# SaLAltimeter_1_5.net
KiCad netlist of a schematic drawn in EAGLE
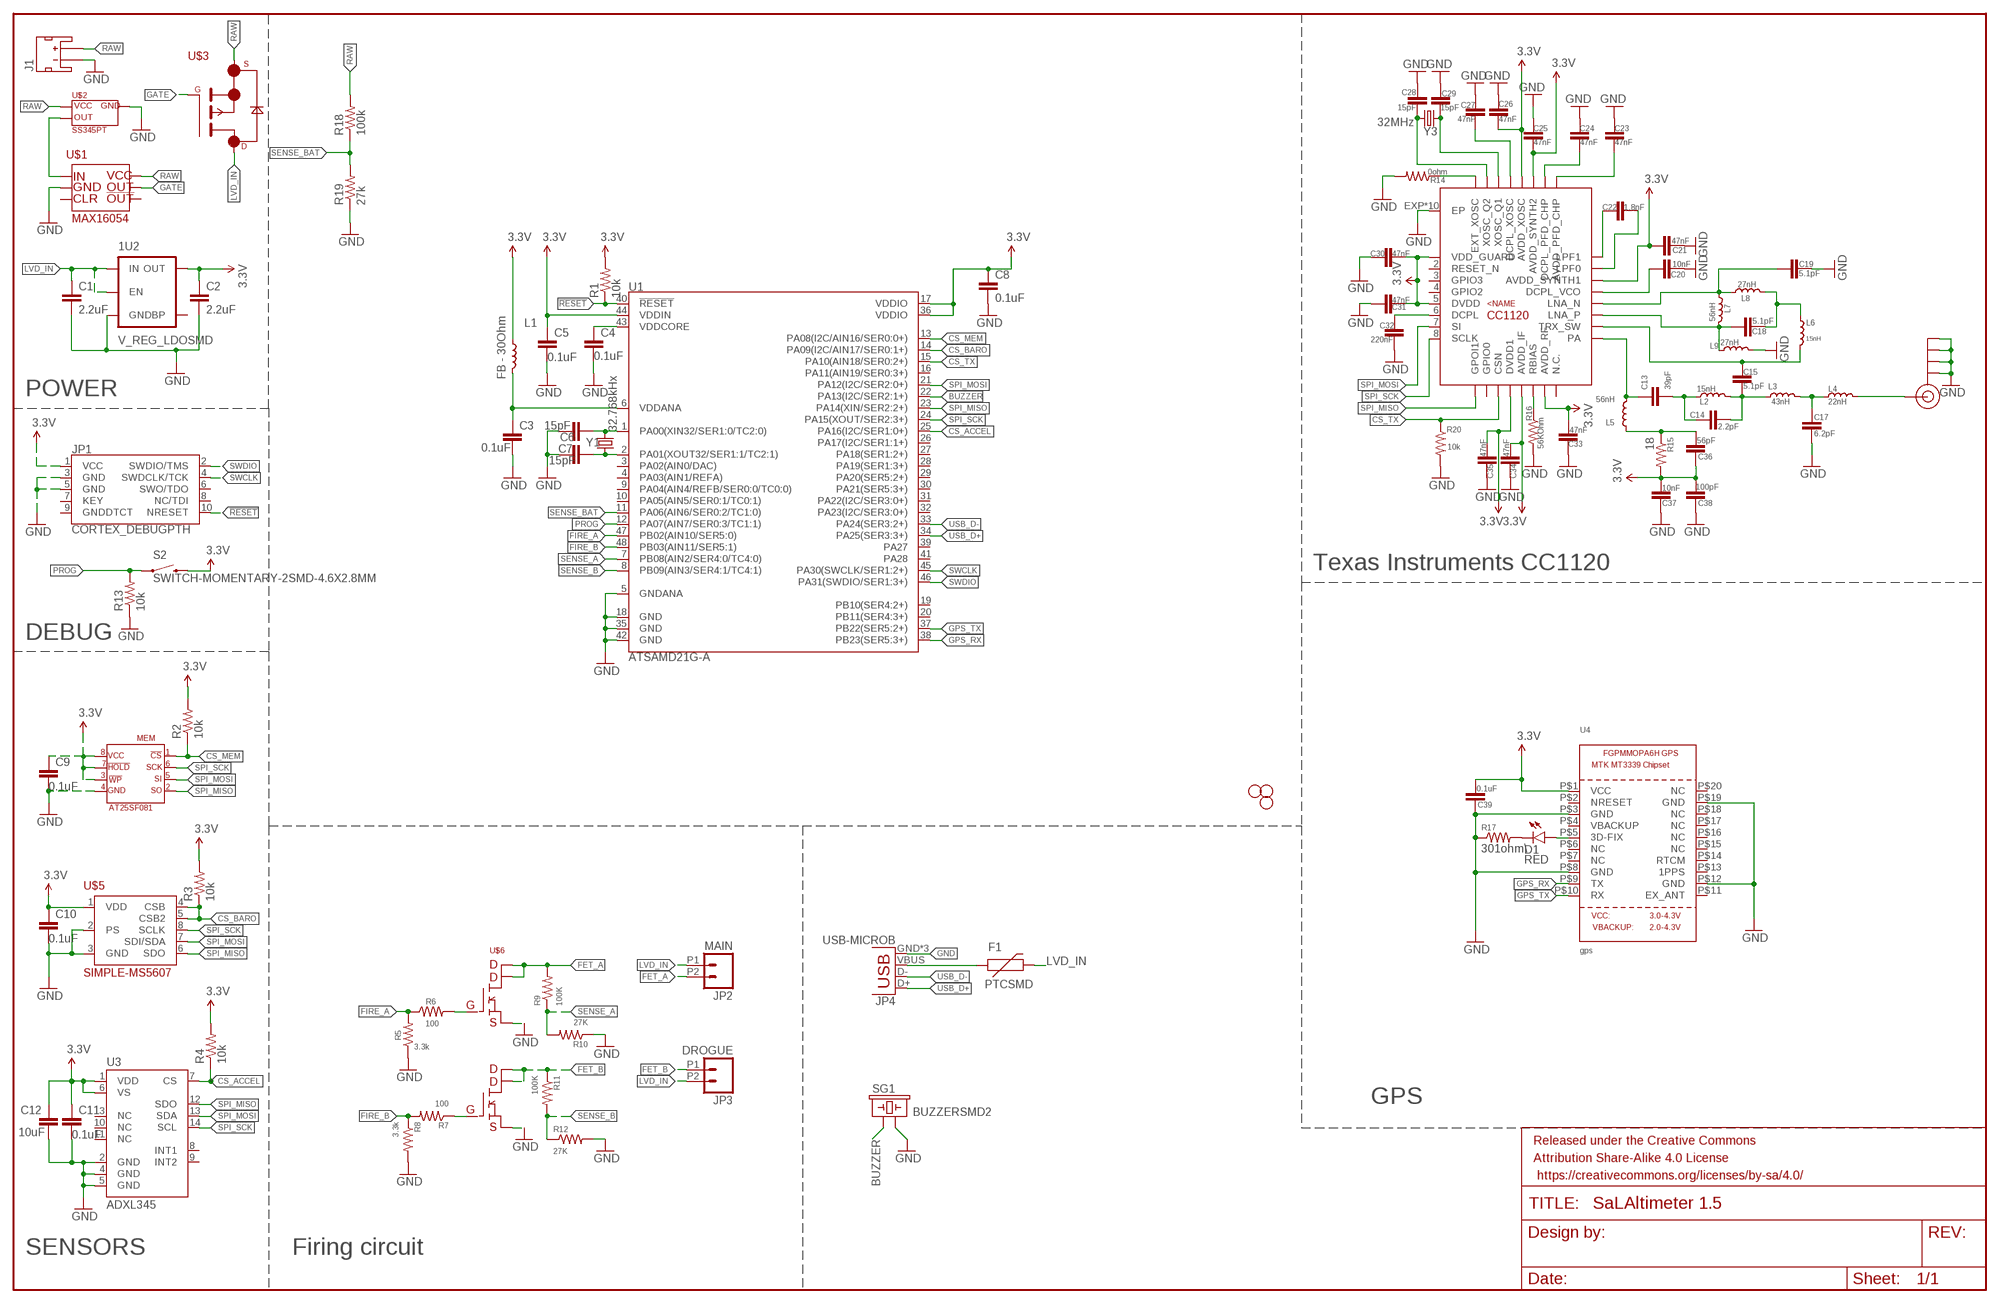
[diagram p0: schematic, sheet 1]

(export (version "E")
  (design (tool "Eeschema 10.0.6"))
  (components
    (comp (ref "1U2")
      (value "V_REG_LDOSMD")
      (footprint "eagle-import:SOT23-5")
      (libsource (lib "eagle-import") (part "V_REG_LDOSMD"))
    )
    (comp (ref "C1")
      (value "2.2uF")
      (footprint "eagle-import:0603-CAP")
      (libsource (lib "eagle-import") (part "CAP0603-CAP"))
    )
    (comp (ref "C2")
      (value "2.2uF")
      (footprint "eagle-import:0603-CAP")
      (libsource (lib "eagle-import") (part "CAP0603-CAP"))
    )
    (comp (ref "C3")
      (value "0.1uF")
      (footprint "eagle-import:0402-CAP")
      (libsource (lib "eagle-import") (part "SparkFun-Passives_CAP0402-CAP"))
    )
    (comp (ref "C4")
      (value "0.1uF")
      (footprint "eagle-import:0402-CAP")
      (libsource (lib "eagle-import") (part "SparkFun-Passives_CAP0402-CAP"))
    )
    (comp (ref "C5")
      (value "0.1uF")
      (footprint "eagle-import:0402-CAP")
      (libsource (lib "eagle-import") (part "SparkFun-Passives_CAP0402-CAP"))
    )
    (comp (ref "C6")
      (value "15pF")
      (footprint "eagle-import:0402-CAP")
      (libsource (lib "eagle-import") (part "SparkFun-Passives_CAP0402-CAP"))
    )
    (comp (ref "C7")
      (value "15pF")
      (footprint "eagle-import:0402-CAP")
      (libsource (lib "eagle-import") (part "SparkFun-Passives_CAP0402-CAP"))
    )
    (comp (ref "C8")
      (value "0.1uF")
      (footprint "eagle-import:0402-CAP")
      (libsource (lib "eagle-import") (part "SparkFun-Passives_CAP0402-CAP"))
    )
    (comp (ref "C9")
      (value "0.1uF")
      (footprint "eagle-import:0402-CAP")
      (libsource (lib "eagle-import") (part "SparkFun-Passives_CAP0402-CAP"))
    )
    (comp (ref "C10")
      (value "0.1uF")
      (footprint "eagle-import:0402-CAP")
      (libsource (lib "eagle-import") (part "SparkFun-Passives_CAP0402-CAP"))
    )
    (comp (ref "C11")
      (value "0.1uF")
      (footprint "eagle-import:0402-CAP")
      (libsource (lib "eagle-import") (part "SparkFun-Passives_CAP0402-CAP"))
    )
    (comp (ref "C12")
      (value "10uF")
      (footprint "eagle-import:0402-CAP")
      (libsource (lib "eagle-import") (part "SparkFun-Passives_CAP0402-CAP"))
    )
    (comp (ref "C13")
      (value "39pF")
      (footprint "eagle-import:0402-CAP")
      (libsource (lib "eagle-import") (part "CAP0402-CAP"))
    )
    (comp (ref "C14")
      (value "2.2pF")
      (footprint "eagle-import:0402-CAP")
      (libsource (lib "eagle-import") (part "CAP0402-CAP"))
    )
    (comp (ref "C15")
      (value "5.1pF")
      (footprint "eagle-import:0402-CAP")
      (libsource (lib "eagle-import") (part "CAP0402-CAP"))
    )
    (comp (ref "C17")
      (value "6.2pF")
      (footprint "eagle-import:0402-CAP")
      (libsource (lib "eagle-import") (part "CAP0402-CAP"))
    )
    (comp (ref "C18")
      (value "5.1pF")
      (footprint "eagle-import:0402-CAP")
      (libsource (lib "eagle-import") (part "CAP0402-CAP"))
    )
    (comp (ref "C19")
      (value "5.1pF")
      (footprint "eagle-import:0402-CAP")
      (libsource (lib "eagle-import") (part "CAP0402-CAP"))
    )
    (comp (ref "C20")
      (value "10nF")
      (footprint "eagle-import:0402-CAP")
      (libsource (lib "eagle-import") (part "CAP0402-CAP"))
    )
    (comp (ref "C21")
      (value "47nF")
      (footprint "eagle-import:0402-CAP")
      (libsource (lib "eagle-import") (part "CAP0402-CAP"))
    )
    (comp (ref "C22")
      (value "1.8nF")
      (footprint "eagle-import:0402-CAP")
      (libsource (lib "eagle-import") (part "CAP0402-CAP"))
    )
    (comp (ref "C23")
      (value "47nF")
      (footprint "eagle-import:0402-CAP")
      (libsource (lib "eagle-import") (part "CAP0402-CAP"))
    )
    (comp (ref "C24")
      (value "47nF")
      (footprint "eagle-import:0402-CAP")
      (libsource (lib "eagle-import") (part "CAP0402-CAP"))
    )
    (comp (ref "C25")
      (value "47nF")
      (footprint "eagle-import:0402-CAP")
      (libsource (lib "eagle-import") (part "CAP0402-CAP"))
    )
    (comp (ref "C26")
      (value "47nF")
      (footprint "eagle-import:0402-CAP")
      (libsource (lib "eagle-import") (part "CAP0402-CAP"))
    )
    (comp (ref "C27")
      (value "47nF")
      (footprint "eagle-import:0402-CAP")
      (libsource (lib "eagle-import") (part "CAP0402-CAP"))
    )
    (comp (ref "C28")
      (value "15pF")
      (footprint "eagle-import:0402-CAP")
      (libsource (lib "eagle-import") (part "CAP0402-CAP"))
    )
    (comp (ref "C29")
      (value "15pF")
      (footprint "eagle-import:0402-CAP")
      (libsource (lib "eagle-import") (part "CAP0402-CAP"))
    )
    (comp (ref "C30")
      (value "47nF")
      (footprint "eagle-import:0402-CAP")
      (libsource (lib "eagle-import") (part "CAP0402-CAP"))
    )
    (comp (ref "C31")
      (value "47nF")
      (footprint "eagle-import:0402-CAP")
      (libsource (lib "eagle-import") (part "CAP0402-CAP"))
    )
    (comp (ref "C32")
      (value "220nF")
      (footprint "eagle-import:0402-CAP")
      (libsource (lib "eagle-import") (part "CAP0402-CAP"))
    )
    (comp (ref "C33")
      (value "47nF")
      (footprint "eagle-import:0402-CAP")
      (libsource (lib "eagle-import") (part "CAP0402-CAP"))
    )
    (comp (ref "C34")
      (value "47nF")
      (footprint "eagle-import:0402-CAP")
      (libsource (lib "eagle-import") (part "CAP0402-CAP"))
    )
    (comp (ref "C35")
      (value "47nF")
      (footprint "eagle-import:0402-CAP")
      (libsource (lib "eagle-import") (part "CAP0402-CAP"))
    )
    (comp (ref "C36")
      (value "56pF")
      (footprint "eagle-import:0402-CAP")
      (libsource (lib "eagle-import") (part "CAP0402-CAP"))
    )
    (comp (ref "C37")
      (value "10nF")
      (footprint "eagle-import:0402-CAP")
      (libsource (lib "eagle-import") (part "CAP0402-CAP"))
    )
    (comp (ref "C38")
      (value "100pF")
      (footprint "eagle-import:0402-CAP")
      (libsource (lib "eagle-import") (part "CAP0402-CAP"))
    )
    (comp (ref "C39")
      (value "0.1uF")
      (footprint "eagle-import:0402-CAP")
      (libsource (lib "eagle-import") (part "CAP0402-CAP"))
    )
    (comp (ref "D1")
      (value "RED")
      (footprint "eagle-import:LED-0603")
      (libsource (lib "eagle-import") (part "LED-RED0603"))
    )
    (comp (ref "F1")
      (value "PTCSMD")
      (footprint "eagle-import:PTC-1206")
      (libsource (lib "eagle-import") (part "PTCSMD"))
    )
    (comp (ref "FRAME1")
      (value "FRAME-LEDGER")
      (footprint "eagle-import:CREATIVE_COMMONS")
      (libsource (lib "eagle-import") (part "FRAME-LEDGER"))
    )
    (comp (ref "J$1")
      (value "SMA_EDGE")
      (footprint "eagle-import:SMA-EDGE")
      (libsource (lib "eagle-import") (part "SMA_EDGE"))
    )
    (comp (ref "J1")
      (value "BAT")
      (footprint "eagle-import:JST-2-SMD")
      (libsource (lib "eagle-import") (part "JST_2MM_MALE"))
    )
    (comp (ref "JP1")
      (value "CORTEX_DEBUGPTH")
      (footprint "eagle-import:2X5-PTH-1.27MM")
      (libsource (lib "eagle-import") (part "CORTEX_DEBUGPTH"))
    )
    (comp (ref "JP2")
      (value "MAIN")
      (footprint "eagle-import:1X02_2.54_SCREWTERM")
      (libsource (lib "eagle-import") (part "M022.54MM_SCREWTERM"))
    )
    (comp (ref "JP3")
      (value "DROGUE")
      (footprint "eagle-import:1X02_2.54_SCREWTERM")
      (libsource (lib "eagle-import") (part "M022.54MM_SCREWTERM"))
    )
    (comp (ref "JP4")
      (value "USB-MICROB")
      (footprint "eagle-import:USB-MICROB")
      (libsource (lib "eagle-import") (part "USB-MICROB"))
    )
    (comp (ref "L1")
      (value "FB - 30Ohm")
      (footprint "eagle-import:0603")
      (libsource (lib "eagle-import") (part "INDUCTOR0603"))
    )
    (comp (ref "L2")
      (value "15nH")
      (footprint "eagle-import:C0402")
      (libsource (lib "eagle-import") (part "INDUCTOR0402"))
    )
    (comp (ref "L3")
      (value "43nH")
      (footprint "eagle-import:C0402")
      (libsource (lib "eagle-import") (part "INDUCTOR0402"))
    )
    (comp (ref "L4")
      (value "22nH")
      (footprint "eagle-import:C0402")
      (libsource (lib "eagle-import") (part "INDUCTOR0402"))
    )
    (comp (ref "L5")
      (value "56nH")
      (footprint "eagle-import:C0402")
      (libsource (lib "eagle-import") (part "INDUCTOR0402"))
    )
    (comp (ref "L6")
      (value "15nH")
      (footprint "eagle-import:C0402")
      (libsource (lib "eagle-import") (part "INDUCTOR0402"))
    )
    (comp (ref "L7")
      (value "56nH")
      (footprint "eagle-import:C0402")
      (libsource (lib "eagle-import") (part "INDUCTOR0402"))
    )
    (comp (ref "L8")
      (value "27nH")
      (footprint "eagle-import:C0402")
      (libsource (lib "eagle-import") (part "INDUCTOR0402"))
    )
    (comp (ref "L9")
      (value "27nH")
      (footprint "eagle-import:C0402")
      (libsource (lib "eagle-import") (part "INDUCTOR0402"))
    )
    (comp (ref "MEM")
      (value "AT25SF081")
      (footprint "eagle-import:AT25SF081")
      (libsource (lib "eagle-import") (part "AT25SF081"))
    )
    (comp (ref "R1")
      (value "10k")
      (footprint "eagle-import:0402-RES")
      (libsource (lib "eagle-import") (part "RESISTOR0402-RES"))
    )
    (comp (ref "R2")
      (value "10k")
      (footprint "eagle-import:0402-RES")
      (libsource (lib "eagle-import") (part "RESISTOR0402-RES"))
    )
    (comp (ref "R3")
      (value "10k")
      (footprint "eagle-import:0402-RES")
      (libsource (lib "eagle-import") (part "RESISTOR0402-RES"))
    )
    (comp (ref "R4")
      (value "10k")
      (footprint "eagle-import:0402-RES")
      (libsource (lib "eagle-import") (part "RESISTOR0402-RES"))
    )
    (comp (ref "R5")
      (value "3.3k")
      (footprint "eagle-import:0402-RES")
      (libsource (lib "eagle-import") (part "RESISTOR0402"))
    )
    (comp (ref "R6")
      (value "100")
      (footprint "eagle-import:0402-RES")
      (libsource (lib "eagle-import") (part "RESISTOR0402"))
    )
    (comp (ref "R7")
      (value "100")
      (footprint "eagle-import:0402-RES")
      (libsource (lib "eagle-import") (part "RESISTOR0402"))
    )
    (comp (ref "R8")
      (value "3.3k")
      (footprint "eagle-import:0402-RES")
      (libsource (lib "eagle-import") (part "RESISTOR0402"))
    )
    (comp (ref "R9")
      (value "100K")
      (footprint "eagle-import:0402-RES")
      (libsource (lib "eagle-import") (part "RESISTOR0402"))
    )
    (comp (ref "R10")
      (value "27K")
      (footprint "eagle-import:0402-RES")
      (libsource (lib "eagle-import") (part "RESISTOR0402"))
    )
    (comp (ref "R11")
      (value "100K")
      (footprint "eagle-import:0402-RES")
      (libsource (lib "eagle-import") (part "RESISTOR0402"))
    )
    (comp (ref "R12")
      (value "27K")
      (footprint "eagle-import:0402-RES")
      (libsource (lib "eagle-import") (part "RESISTOR0402"))
    )
    (comp (ref "R13")
      (value "10k")
      (footprint "eagle-import:0402-RES")
      (libsource (lib "eagle-import") (part "RESISTOR0402-RES"))
    )
    (comp (ref "R14")
      (value "0ohm")
      (footprint "eagle-import:0402-RES")
      (libsource (lib "eagle-import") (part "RESISTOR0402-RES"))
    )
    (comp (ref "R15")
      (value "18")
      (footprint "eagle-import:0402-RES")
      (libsource (lib "eagle-import") (part "RESISTOR0402-RES"))
    )
    (comp (ref "R16")
      (value "56KOhm")
      (footprint "eagle-import:0402-RES")
      (libsource (lib "eagle-import") (part "RESISTOR0402-RES"))
    )
    (comp (ref "R17")
      (value "301ohm\\")
      (footprint "eagle-import:0402-RES")
      (libsource (lib "eagle-import") (part "RESISTOR0402-RES"))
    )
    (comp (ref "R18")
      (value "100k")
      (footprint "eagle-import:0402-RES")
      (libsource (lib "eagle-import") (part "RESISTOR0402-RES"))
    )
    (comp (ref "R19")
      (value "27k")
      (footprint "eagle-import:0402-RES")
      (libsource (lib "eagle-import") (part "RESISTOR0402-RES"))
    )
    (comp (ref "R20")
      (value "10k")
      (footprint "eagle-import:0402-RES")
      (libsource (lib "eagle-import") (part "RESISTOR0402-RES"))
    )
    (comp (ref "S2")
      (value "SWITCH-MOMENTARY-2SMD-4.6X2.8MM")
      (footprint "eagle-import:TACTILE_SWITCH_SMD_4.6X2.8MM")
      (libsource (lib "eagle-import") (part "SWITCH-MOMENTARY-2SMD-4.6X2.8MM"))
    )
    (comp (ref "SG1")
      (value "BUZZERSMD2")
      (footprint "eagle-import:BUZZER-CCV")
      (libsource (lib "eagle-import") (part "BUZZERSMD2"))
    )
    (comp (ref "STANDOFF1")
      (value "STAND-OFF")
      (footprint "eagle-import:STAND-OFF")
      (libsource (lib "eagle-import") (part "STAND-OFF"))
    )
    (comp (ref "STANDOFF2")
      (value "STAND-OFF")
      (footprint "eagle-import:STAND-OFF")
      (libsource (lib "eagle-import") (part "STAND-OFF"))
    )
    (comp (ref "STANDOFF3")
      (value "STAND-OFF")
      (footprint "eagle-import:STAND-OFF")
      (libsource (lib "eagle-import") (part "STAND-OFF"))
    )
    (comp (ref "U$1")
      (value "MAX16054")
      (footprint "eagle-import:MAX16054")
      (libsource (lib "eagle-import") (part "MAX16054"))
    )
    (comp (ref "U$2")
      (value "SS345PT")
      (footprint "eagle-import:SS345PT")
      (libsource (lib "eagle-import") (part "SS345PT"))
    )
    (comp (ref "U$3")
      (value "SI7615ADN")
      (footprint "eagle-import:SI7615ADN")
      (libsource (lib "eagle-import") (part "SI7615ADN"))
    )
    (comp (ref "U$5")
      (value "SIMPLE-MS5607")
      (footprint "eagle-import:MS5607")
      (libsource (lib "eagle-import") (part "SIMPLE-MS5607"))
    )
    (comp (ref "U$6")
      (value "SI7232DN")
      (footprint "eagle-import:SI7232DN")
      (libsource (lib "eagle-import") (part "SI7232DN"))
    )
    (comp (ref "U1")
      (value "ATSAMD21G-A")
      (footprint "eagle-import:TQFP-48")
      (libsource (lib "eagle-import") (part "ATSAMD21G-A"))
    )
    (comp (ref "U2")
      (value "CC1120")
      (footprint "eagle-import:CC1120")
      (libsource (lib "eagle-import") (part "CC1120"))
    )
    (comp (ref "U3")
      (value "ADXL345")
      (footprint "eagle-import:LGA14")
      (libsource (lib "eagle-import") (part "ADXL345"))
    )
    (comp (ref "U4")
      (value "gps")
      (footprint "eagle-import:FGPMMOPA6H")
      (libsource (lib "eagle-import") (part "GPS_FGPMMOPA6H"))
    )
    (comp (ref "Y1")
      (value "32.768kHx")
      (footprint "eagle-import:CRYSTAL-SMD-3.2X1.5MM")
      (libsource (lib "eagle-import") (part "CRYSTAL3.2X1.5MM"))
    )
    (comp (ref "Y3")
      (value "32MHz")
      (footprint "eagle-import:CRYSTAL-SMD-5X3")
      (libsource (lib "eagle-import") (part "CRYSTAL5X3"))
    )
  )
  (nets
    (net (code "1") (name "/~{RESET}") (class "Default")
      (node (ref "JP1") (pin "10") (pinfunction "NRESET_10") (pintype "bidirectional"))
      (node (ref "R1") (pin "1") (pinfunction "1_1") (pintype "passive"))
      (node (ref "U1") (pin "40") (pinfunction "~{RESET}_40") (pintype "bidirectional"))
    )
    (net (code "2") (name "3.3V") (class "Default")
      (node (ref "1U2") (pin "5") (pinfunction "OUT_5") (pintype "passive"))
      (node (ref "C10") (pin "1") (pinfunction "1_1") (pintype "passive"))
      (node (ref "C11") (pin "1") (pinfunction "1_1") (pintype "passive"))
      (node (ref "C12") (pin "1") (pinfunction "1_1") (pintype "passive"))
      (node (ref "C2") (pin "1") (pinfunction "1_1") (pintype "passive"))
      (node (ref "C21") (pin "1") (pinfunction "1_1") (pintype "passive"))
      (node (ref "C25") (pin "2") (pinfunction "2_2") (pintype "passive"))
      (node (ref "C26") (pin "2") (pinfunction "2_2") (pintype "passive"))
      (node (ref "C30") (pin "2") (pinfunction "2_2") (pintype "passive"))
      (node (ref "C31") (pin "2") (pinfunction "2_2") (pintype "passive"))
      (node (ref "C33") (pin "2") (pinfunction "2_2") (pintype "passive"))
      (node (ref "C34") (pin "2") (pinfunction "2_2") (pintype "passive"))
      (node (ref "C35") (pin "2") (pinfunction "2_2") (pintype "passive"))
      (node (ref "C36") (pin "1") (pinfunction "1_1") (pintype "passive"))
      (node (ref "C37") (pin "2") (pinfunction "2_2") (pintype "passive"))
      (node (ref "C38") (pin "2") (pinfunction "2_2") (pintype "passive"))
      (node (ref "C39") (pin "2") (pinfunction "2_2") (pintype "passive"))
      (node (ref "C5") (pin "1") (pinfunction "1_1") (pintype "passive"))
      (node (ref "C8") (pin "1") (pinfunction "1_1") (pintype "passive"))
      (node (ref "C9") (pin "1") (pinfunction "1_1") (pintype "passive"))
      (node (ref "JP1") (pin "1") (pinfunction "VCC_1") (pintype "bidirectional"))
      (node (ref "L1") (pin "1") (pinfunction "1_1") (pintype "passive"))
      (node (ref "MEM") (pin "!HOLD") (pinfunction "~{HOLD}_!HOLD") (pintype "bidirectional"))
      (node (ref "MEM") (pin "!WP") (pinfunction "~{WP}_!WP") (pintype "bidirectional"))
      (node (ref "MEM") (pin "VCC") (pinfunction "VCC_VCC") (pintype "bidirectional"))
      (node (ref "R1") (pin "2") (pinfunction "2_2") (pintype "passive"))
      (node (ref "R15") (pin "2") (pinfunction "2_2") (pintype "passive"))
      (node (ref "R2") (pin "2") (pinfunction "2_2") (pintype "passive"))
      (node (ref "R3") (pin "2") (pinfunction "2_2") (pintype "passive"))
      (node (ref "R4") (pin "2") (pinfunction "2_2") (pintype "passive"))
      (node (ref "S2") (pin "3") (pinfunction "2_3") (pintype "passive"))
      (node (ref "S2") (pin "4") (pinfunction "2_4") (pintype "passive"))
      (node (ref "U$5") (pin "1") (pinfunction "VDD_1") (pintype "bidirectional"))
      (node (ref "U1") (pin "17") (pinfunction "VDDIO_17") (pintype "bidirectional"))
      (node (ref "U1") (pin "36") (pinfunction "VDDIO_36") (pintype "bidirectional"))
      (node (ref "U1") (pin "44") (pinfunction "VDDIN_44") (pintype "bidirectional"))
      (node (ref "U2") (pin "1") (pinfunction "VDD_GUARD_1") (pintype "bidirectional"))
      (node (ref "U2") (pin "12") (pinfunction "DVDD1_12") (pintype "bidirectional"))
      (node (ref "U2") (pin "13") (pinfunction "AVDD_IF_13") (pintype "bidirectional"))
      (node (ref "U2") (pin "15") (pinfunction "AVDD_RF_15") (pintype "bidirectional"))
      (node (ref "U2") (pin "22") (pinfunction "AVDD_SYNTH1_22") (pintype "bidirectional"))
      (node (ref "U2") (pin "27") (pinfunction "AVDD_SYNTH2_27") (pintype "bidirectional"))
      (node (ref "U2") (pin "28") (pinfunction "AVDD_XOSC_28") (pintype "bidirectional"))
      (node (ref "U2") (pin "5") (pinfunction "DVDD_5") (pintype "bidirectional"))
      (node (ref "U3") (pin "1") (pinfunction "VDD_1") (pintype "bidirectional"))
      (node (ref "U3") (pin "6") (pinfunction "VS_6") (pintype "bidirectional"))
      (node (ref "U4") (pin "P$1") (pinfunction "VCC_P$1") (pintype "bidirectional"))
    )
    (net (code "3") (name "BUZZER") (class "Default")
      (node (ref "SG1") (pin "+") (pinfunction "1_+") (pintype "passive"))
      (node (ref "U1") (pin "22") (pinfunction "PA13(I2C/SER2:1+)_22") (pintype "bidirectional"))
    )
    (net (code "4") (name "CS_ACCEL") (class "Default")
      (node (ref "R4") (pin "1") (pinfunction "1_1") (pintype "passive"))
      (node (ref "U1") (pin "25") (pinfunction "PA16(I2C/SER1:0+)_25") (pintype "bidirectional"))
      (node (ref "U3") (pin "7") (pinfunction "CS_7") (pintype "bidirectional"))
    )
    (net (code "5") (name "CS_BARO") (class "Default")
      (node (ref "R3") (pin "1") (pinfunction "1_1") (pintype "passive"))
      (node (ref "U$5") (pin "4") (pinfunction "CSB_4") (pintype "bidirectional"))
      (node (ref "U$5") (pin "5") (pinfunction "CSB2_5") (pintype "bidirectional"))
      (node (ref "U1") (pin "14") (pinfunction "PA09(I2C/AIN17/SER0:1+)_14") (pintype "bidirectional"))
    )
    (net (code "6") (name "CS_MEM") (class "Default")
      (node (ref "MEM") (pin "!CS") (pinfunction "~{CS}_!CS") (pintype "bidirectional"))
      (node (ref "R2") (pin "1") (pinfunction "1_1") (pintype "passive"))
      (node (ref "U1") (pin "13") (pinfunction "PA08(I2C/AIN16/SER0:0+)_13") (pintype "bidirectional"))
    )
    (net (code "7") (name "CS_TX") (class "Default")
      (node (ref "R20") (pin "1") (pinfunction "1_1") (pintype "passive"))
      (node (ref "U1") (pin "15") (pinfunction "PA10(AIN18/SER0:2+)_15") (pintype "bidirectional"))
      (node (ref "U2") (pin "11") (pinfunction "CSN_11") (pintype "bidirectional"))
    )
    (net (code "8") (name "FET_A") (class "Default")
      (node (ref "JP2") (pin "P2") (pinfunction "2_P2") (pintype "passive"))
      (node (ref "R9") (pin "2") (pinfunction "2_2") (pintype "passive"))
      (node (ref "U$6") (pin "7") (pinfunction "PIN7_7") (pintype "bidirectional"))
      (node (ref "U$6") (pin "8") (pinfunction "PIN8_8") (pintype "bidirectional"))
    )
    (net (code "9") (name "FET_B") (class "Default")
      (node (ref "JP3") (pin "P1") (pinfunction "1_P1") (pintype "passive"))
      (node (ref "R11") (pin "1") (pinfunction "1_1") (pintype "passive"))
      (node (ref "U$6") (pin "5") (pinfunction "PIN5_5") (pintype "bidirectional"))
      (node (ref "U$6") (pin "6") (pinfunction "PIN6_6") (pintype "bidirectional"))
    )
    (net (code "10") (name "FIRE_A") (class "Default")
      (node (ref "R5") (pin "2") (pinfunction "2_2") (pintype "passive"))
      (node (ref "R6") (pin "1") (pinfunction "1_1") (pintype "passive"))
      (node (ref "U1") (pin "47") (pinfunction "PB02(AIN10/SER5:0)_47") (pintype "bidirectional"))
    )
    (net (code "11") (name "FIRE_B") (class "Default")
      (node (ref "R7") (pin "2") (pinfunction "2_2") (pintype "passive"))
      (node (ref "R8") (pin "1") (pinfunction "1_1") (pintype "passive"))
      (node (ref "U1") (pin "48") (pinfunction "PB03(AIN11/SER5:1)_48") (pintype "bidirectional"))
    )
    (net (code "12") (name "GATE") (class "Default")
      (node (ref "U$1") (pin "OUT") (pinfunction "OUT_OUT") (pintype "bidirectional"))
      (node (ref "U$3") (pin "G") (pinfunction "G_G") (pintype "bidirectional"))
    )
    (net (code "13") (name "GND") (class "Default")
      (node (ref "1U2") (pin "2") (pinfunction "GND_2") (pintype "input"))
      (node (ref "C1") (pin "2") (pinfunction "2_2") (pintype "passive"))
      (node (ref "C10") (pin "2") (pinfunction "2_2") (pintype "passive"))
      (node (ref "C11") (pin "2") (pinfunction "2_2") (pintype "passive"))
      (node (ref "C12") (pin "2") (pinfunction "2_2") (pintype "passive"))
      (node (ref "C17") (pin "2") (pinfunction "2_2") (pintype "passive"))
      (node (ref "C19") (pin "2") (pinfunction "2_2") (pintype "passive"))
      (node (ref "C2") (pin "2") (pinfunction "2_2") (pintype "passive"))
      (node (ref "C20") (pin "2") (pinfunction "2_2") (pintype "passive"))
      (node (ref "C21") (pin "2") (pinfunction "2_2") (pintype "passive"))
      (node (ref "C23") (pin "1") (pinfunction "1_1") (pintype "passive"))
      (node (ref "C24") (pin "1") (pinfunction "1_1") (pintype "passive"))
      (node (ref "C25") (pin "1") (pinfunction "1_1") (pintype "passive"))
      (node (ref "C26") (pin "1") (pinfunction "1_1") (pintype "passive"))
      (node (ref "C27") (pin "1") (pinfunction "1_1") (pintype "passive"))
      (node (ref "C28") (pin "1") (pinfunction "1_1") (pintype "passive"))
      (node (ref "C29") (pin "1") (pinfunction "1_1") (pintype "passive"))
      (node (ref "C3") (pin "2") (pinfunction "2_2") (pintype "passive"))
      (node (ref "C30") (pin "1") (pinfunction "1_1") (pintype "passive"))
      (node (ref "C31") (pin "1") (pinfunction "1_1") (pintype "passive"))
      (node (ref "C32") (pin "1") (pinfunction "1_1") (pintype "passive"))
      (node (ref "C33") (pin "1") (pinfunction "1_1") (pintype "passive"))
      (node (ref "C34") (pin "1") (pinfunction "1_1") (pintype "passive"))
      (node (ref "C35") (pin "1") (pinfunction "1_1") (pintype "passive"))
      (node (ref "C37") (pin "1") (pinfunction "1_1") (pintype "passive"))
      (node (ref "C38") (pin "1") (pinfunction "1_1") (pintype "passive"))
      (node (ref "C39") (pin "1") (pinfunction "1_1") (pintype "passive"))
      (node (ref "C4") (pin "2") (pinfunction "2_2") (pintype "passive"))
      (node (ref "C5") (pin "2") (pinfunction "2_2") (pintype "passive"))
      (node (ref "C6") (pin "2") (pinfunction "2_2") (pintype "passive"))
      (node (ref "C7") (pin "2") (pinfunction "2_2") (pintype "passive"))
      (node (ref "C8") (pin "2") (pinfunction "2_2") (pintype "passive"))
      (node (ref "C9") (pin "2") (pinfunction "2_2") (pintype "passive"))
      (node (ref "J$1") (pin "GND@0") (pinfunction "GND_GND@0") (pintype "bidirectional"))
      (node (ref "J$1") (pin "GND@1") (pinfunction "GND_GND@1") (pintype "bidirectional"))
      (node (ref "J$1") (pin "GND@2") (pinfunction "GND_GND@2") (pintype "bidirectional"))
      (node (ref "J$1") (pin "GND@3") (pinfunction "GND_GND@3") (pintype "bidirectional"))
      (node (ref "J1") (pin "1") (pinfunction "-_1") (pintype "bidirectional"))
      (node (ref "JP1") (pin "3") (pinfunction "GND_3") (pintype "bidirectional"))
      (node (ref "JP1") (pin "5") (pinfunction "GND_5") (pintype "bidirectional"))
      (node (ref "JP4") (pin "GND") (pinfunction "GND_GND") (pintype "bidirectional"))
      (node (ref "JP4") (pin "MT1") (pinfunction "GND_MT1") (pintype "bidirectional"))
      (node (ref "JP4") (pin "MT2") (pinfunction "GND_MT2") (pintype "bidirectional"))
      (node (ref "L9") (pin "2") (pinfunction "2_2") (pintype "passive"))
      (node (ref "MEM") (pin "GND") (pinfunction "GND_GND") (pintype "bidirectional"))
      (node (ref "R10") (pin "1") (pinfunction "1_1") (pintype "passive"))
      (node (ref "R12") (pin "2") (pinfunction "2_2") (pintype "passive"))
      (node (ref "R13") (pin "1") (pinfunction "1_1") (pintype "passive"))
      (node (ref "R14") (pin "2") (pinfunction "2_2") (pintype "passive"))
      (node (ref "R16") (pin "2") (pinfunction "2_2") (pintype "passive"))
      (node (ref "R17") (pin "1") (pinfunction "1_1") (pintype "passive"))
      (node (ref "R19") (pin "1") (pinfunction "1_1") (pintype "passive"))
      (node (ref "R20") (pin "2") (pinfunction "2_2") (pintype "passive"))
      (node (ref "R5") (pin "1") (pinfunction "1_1") (pintype "passive"))
      (node (ref "R8") (pin "2") (pinfunction "2_2") (pintype "passive"))
      (node (ref "SG1") (pin "-") (pinfunction "2_-") (pintype "passive"))
      (node (ref "U$1") (pin "GND") (pinfunction "GND_GND") (pintype "bidirectional"))
      (node (ref "U$2") (pin "GND") (pinfunction "GND_GND") (pintype "bidirectional"))
      (node (ref "U$5") (pin "2") (pinfunction "PS_2") (pintype "bidirectional"))
      (node (ref "U$5") (pin "3") (pinfunction "GND_3") (pintype "bidirectional"))
      (node (ref "U$6") (pin "1") (pinfunction "PIN1_1") (pintype "bidirectional"))
      (node (ref "U$6") (pin "3") (pinfunction "PIN3_3") (pintype "bidirectional"))
      (node (ref "U1") (pin "18") (pinfunction "GND_18") (pintype "bidirectional"))
      (node (ref "U1") (pin "35") (pinfunction "GND_35") (pintype "bidirectional"))
      (node (ref "U1") (pin "42") (pinfunction "GND_42") (pintype "bidirectional"))
      (node (ref "U1") (pin "5") (pinfunction "GNDANA_5") (pintype "bidirectional"))
      (node (ref "U2") (pin "EXP") (pinfunction "EP_EXP") (pintype "bidirectional"))
      (node (ref "U2") (pin "EXP@1") (pinfunction "EP_EXP@1") (pintype "bidirectional"))
      (node (ref "U2") (pin "EXP@2") (pinfunction "EP_EXP@2") (pintype "bidirectional"))
      (node (ref "U2") (pin "EXP@3") (pinfunction "EP_EXP@3") (pintype "bidirectional"))
      (node (ref "U2") (pin "EXP@4") (pinfunction "EP_EXP@4") (pintype "bidirectional"))
      (node (ref "U2") (pin "EXP@5") (pinfunction "EP_EXP@5") (pintype "bidirectional"))
      (node (ref "U2") (pin "EXP@6") (pinfunction "EP_EXP@6") (pintype "bidirectional"))
      (node (ref "U2") (pin "EXP@7") (pinfunction "EP_EXP@7") (pintype "bidirectional"))
      (node (ref "U2") (pin "EXP@8") (pinfunction "EP_EXP@8") (pintype "bidirectional"))
      (node (ref "U2") (pin "EXP@9") (pinfunction "EP_EXP@9") (pintype "bidirectional"))
      (node (ref "U3") (pin "2") (pinfunction "GND_2") (pintype "bidirectional"))
      (node (ref "U3") (pin "4") (pinfunction "GND_4") (pintype "bidirectional"))
      (node (ref "U3") (pin "5") (pinfunction "GND_5") (pintype "bidirectional"))
      (node (ref "U4") (pin "P$12") (pinfunction "GND_P$12") (pintype "bidirectional"))
      (node (ref "U4") (pin "P$19") (pinfunction "GND_P$19") (pintype "bidirectional"))
      (node (ref "U4") (pin "P$3") (pinfunction "GND_P$3") (pintype "bidirectional"))
      (node (ref "U4") (pin "P$8") (pinfunction "GND_P$8") (pintype "bidirectional"))
    )
    (net (code "14") (name "GPS_RX") (class "Default")
      (node (ref "U1") (pin "38") (pinfunction "PB23(SER5:3+)_38") (pintype "bidirectional"))
      (node (ref "U4") (pin "P$9") (pinfunction "TX_P$9") (pintype "bidirectional"))
    )
    (net (code "15") (name "GPS_TX") (class "Default")
      (node (ref "U1") (pin "37") (pinfunction "PB22(SER5:2+)_37") (pintype "bidirectional"))
      (node (ref "U4") (pin "P$10") (pinfunction "RX_P$10") (pintype "bidirectional"))
    )
    (net (code "16") (name "LVD_IN") (class "Default")
      (node (ref "1U2") (pin "1") (pinfunction "IN_1") (pintype "input"))
      (node (ref "1U2") (pin "3") (pinfunction "EN_3") (pintype "input"))
      (node (ref "C1") (pin "1") (pinfunction "1_1") (pintype "passive"))
      (node (ref "F1") (pin "2") (pinfunction "2_2") (pintype "bidirectional"))
      (node (ref "JP2") (pin "P1") (pinfunction "1_P1") (pintype "passive"))
      (node (ref "JP3") (pin "P2") (pinfunction "2_P2") (pintype "passive"))
      (node (ref "U$3") (pin "D1") (pinfunction "D_D1") (pintype "bidirectional"))
      (node (ref "U$3") (pin "D2") (pinfunction "D_D2") (pintype "bidirectional"))
      (node (ref "U$3") (pin "D3") (pinfunction "D_D3") (pintype "bidirectional"))
      (node (ref "U$3") (pin "D4") (pinfunction "D_D4") (pintype "bidirectional"))
    )
    (net (code "17") (name "Net-(C13-Pad2)") (class "Default")
      (node (ref "C13") (pin "2") (pinfunction "2_2") (pintype "passive"))
      (node (ref "C14") (pin "1") (pinfunction "1_1") (pintype "passive"))
      (node (ref "L2") (pin "1") (pinfunction "1_1") (pintype "passive"))
    )
    (net (code "18") (name "Net-(C14-Pad2)") (class "Default")
      (node (ref "C14") (pin "2") (pinfunction "2_2") (pintype "passive"))
      (node (ref "C15") (pin "1") (pinfunction "1_1") (pintype "passive"))
      (node (ref "L2") (pin "2") (pinfunction "2_2") (pintype "passive"))
      (node (ref "L3") (pin "1") (pinfunction "1_1") (pintype "passive"))
    )
    (net (code "19") (name "Net-(C17-Pad1)") (class "Default")
      (node (ref "C17") (pin "1") (pinfunction "1_1") (pintype "passive"))
      (node (ref "L3") (pin "2") (pinfunction "2_2") (pintype "passive"))
      (node (ref "L4") (pin "1") (pinfunction "1_1") (pintype "passive"))
    )
    (net (code "20") (name "Net-(C18-Pad2)") (class "Default")
      (node (ref "C18") (pin "2") (pinfunction "2_2") (pintype "passive"))
      (node (ref "L6") (pin "1") (pinfunction "1_1") (pintype "passive"))
      (node (ref "L8") (pin "2") (pinfunction "2_2") (pintype "passive"))
    )
    (net (code "21") (name "Net-(C36-Pad2)") (class "Default")
      (node (ref "C36") (pin "2") (pinfunction "2_2") (pintype "passive"))
      (node (ref "L5") (pin "1") (pinfunction "1_1") (pintype "passive"))
      (node (ref "R15") (pin "1") (pinfunction "1_1") (pintype "passive"))
    )
    (net (code "22") (name "Net-(D1-PadC)") (class "Default")
      (node (ref "D1") (pin "C") (pinfunction "C_C") (pintype "passive"))
      (node (ref "R17") (pin "2") (pinfunction "2_2") (pintype "passive"))
    )
    (net (code "23") (name "Net-(F1-Pad1)") (class "Default")
      (node (ref "F1") (pin "1") (pinfunction "1_1") (pintype "bidirectional"))
      (node (ref "JP4") (pin "VBUS") (pinfunction "VBUS_VBUS") (pintype "bidirectional"))
    )
    (net (code "24") (name "Net-(J$1-SIGNAL)") (class "Default")
      (node (ref "J$1") (pin "SIG") (pinfunction "SIGNAL_SIG") (pintype "bidirectional"))
      (node (ref "L4") (pin "2") (pinfunction "2_2") (pintype "passive"))
    )
    (net (code "25") (name "Net-(U$1-PadIN)") (class "Default")
      (node (ref "U$1") (pin "IN") (pinfunction "IN_IN") (pintype "bidirectional"))
      (node (ref "U$2") (pin "OUT") (pinfunction "OUT_OUT") (pintype "bidirectional"))
    )
    (net (code "26") (name "Net-(U$6-PIN2)") (class "Default")
      (node (ref "R6") (pin "2") (pinfunction "2_2") (pintype "passive"))
      (node (ref "U$6") (pin "2") (pinfunction "PIN2_2") (pintype "bidirectional"))
    )
    (net (code "27") (name "Net-(U$6-PIN4)") (class "Default")
      (node (ref "R7") (pin "1") (pinfunction "1_1") (pintype "passive"))
      (node (ref "U$6") (pin "4") (pinfunction "PIN4_4") (pintype "bidirectional"))
    )
    (net (code "28") (name "Net-(U1-PA00(XIN32{slash}SER1:0{slash}TC2:0))") (class "Default")
      (node (ref "C6") (pin "1") (pinfunction "1_1") (pintype "passive"))
      (node (ref "U1") (pin "1") (pinfunction "PA00(XIN32/SER1:0/TC2:0)_1") (pintype "bidirectional"))
      (node (ref "Y1") (pin "P$2") (pinfunction "2_P$2") (pintype "passive"))
    )
    (net (code "29") (name "Net-(U1-PA01(XOUT32{slash}SER1:1{slash}TC2:1))") (class "Default")
      (node (ref "C7") (pin "1") (pinfunction "1_1") (pintype "passive"))
      (node (ref "U1") (pin "2") (pinfunction "PA01(XOUT32/SER1:1/TC2:1)_2") (pintype "bidirectional"))
      (node (ref "Y1") (pin "P$1") (pinfunction "1_P$1") (pintype "passive"))
    )
    (net (code "30") (name "Net-(U1-VDDANA)") (class "Default")
      (node (ref "C3") (pin "1") (pinfunction "1_1") (pintype "passive"))
      (node (ref "L1") (pin "2") (pinfunction "2_2") (pintype "passive"))
      (node (ref "U1") (pin "6") (pinfunction "VDDANA_6") (pintype "bidirectional"))
    )
    (net (code "31") (name "Net-(U1-VDDCORE)") (class "Default")
      (node (ref "C4") (pin "1") (pinfunction "1_1") (pintype "passive"))
      (node (ref "U1") (pin "43") (pinfunction "VDDCORE_43") (pintype "bidirectional"))
    )
    (net (code "32") (name "Net-(U2-AVDD_PFD_CHP)") (class "Default")
      (node (ref "C23") (pin "2") (pinfunction "2_2") (pintype "passive"))
      (node (ref "U2") (pin "25") (pinfunction "AVDD_PFD_CHP_25") (pintype "bidirectional"))
    )
    (net (code "33") (name "Net-(U2-DCPL)") (class "Default")
      (node (ref "C32") (pin "2") (pinfunction "2_2") (pintype "passive"))
      (node (ref "U2") (pin "6") (pinfunction "DCPL_6") (pintype "bidirectional"))
    )
    (net (code "34") (name "Net-(U2-DCPL_PFD_CHP)") (class "Default")
      (node (ref "C24") (pin "2") (pinfunction "2_2") (pintype "passive"))
      (node (ref "U2") (pin "26") (pinfunction "DCPL_PFD_CHP_26") (pintype "bidirectional"))
    )
    (net (code "35") (name "Net-(U2-DCPL_VCO)") (class "Default")
      (node (ref "C20") (pin "1") (pinfunction "1_1") (pintype "passive"))
      (node (ref "U2") (pin "21") (pinfunction "DCPL_VCO_21") (pintype "bidirectional"))
    )
    (net (code "36") (name "Net-(U2-DCPL_XOSC)") (class "Default")
      (node (ref "C27") (pin "2") (pinfunction "2_2") (pintype "passive"))
      (node (ref "U2") (pin "29") (pinfunction "DCPL_XOSC_29") (pintype "bidirectional"))
    )
    (net (code "37") (name "Net-(U2-EXT_XOSC)") (class "Default")
      (node (ref "R14") (pin "1") (pinfunction "1_1") (pintype "passive"))
      (node (ref "U2") (pin "32") (pinfunction "EXT_XOSC_32") (pintype "bidirectional"))
    )
    (net (code "38") (name "Net-(U2-LNA_N)") (class "Default")
      (node (ref "C19") (pin "1") (pinfunction "1_1") (pintype "passive"))
      (node (ref "L7") (pin "1") (pinfunction "1_1") (pintype "passive"))
      (node (ref "L8") (pin "1") (pinfunction "1_1") (pintype "passive"))
      (node (ref "U2") (pin "20") (pinfunction "LNA_N_20") (pintype "bidirectional"))
    )
    (net (code "39") (name "Net-(U2-LNA_P)") (class "Default")
      (node (ref "C18") (pin "1") (pinfunction "1_1") (pintype "passive"))
      (node (ref "L7") (pin "2") (pinfunction "2_2") (pintype "passive"))
      (node (ref "L9") (pin "1") (pinfunction "1_1") (pintype "passive"))
      (node (ref "U2") (pin "19") (pinfunction "LNA_P_19") (pintype "bidirectional"))
    )
    (net (code "40") (name "Net-(U2-LPF0)") (class "Default")
      (node (ref "C22") (pin "2") (pinfunction "2_2") (pintype "passive"))
      (node (ref "U2") (pin "23") (pinfunction "LPF0_23") (pintype "bidirectional"))
    )
    (net (code "41") (name "Net-(U2-LPF1)") (class "Default")
      (node (ref "C22") (pin "1") (pinfunction "1_1") (pintype "passive"))
      (node (ref "U2") (pin "24") (pinfunction "LPF1_24") (pintype "bidirectional"))
    )
    (net (code "42") (name "Net-(U2-PA)") (class "Default")
      (node (ref "C13") (pin "1") (pinfunction "1_1") (pintype "passive"))
      (node (ref "L5") (pin "2") (pinfunction "2_2") (pintype "passive"))
      (node (ref "U2") (pin "17") (pinfunction "PA_17") (pintype "bidirectional"))
    )
    (net (code "43") (name "Net-(U2-RBIAS)") (class "Default")
      (node (ref "R16") (pin "1") (pinfunction "1_1") (pintype "passive"))
      (node (ref "U2") (pin "14") (pinfunction "RBIAS_14") (pintype "bidirectional"))
    )
    (net (code "44") (name "Net-(U2-TRX_SW)") (class "Default")
      (node (ref "C15") (pin "2") (pinfunction "2_2") (pintype "passive"))
      (node (ref "L6") (pin "2") (pinfunction "2_2") (pintype "passive"))
      (node (ref "U2") (pin "18") (pinfunction "TRX_SW_18") (pintype "bidirectional"))
    )
    (net (code "45") (name "Net-(U2-XOSC_Q1)") (class "Default")
      (node (ref "C29") (pin "2") (pinfunction "2_2") (pintype "passive"))
      (node (ref "U2") (pin "30") (pinfunction "XOSC_Q1_30") (pintype "bidirectional"))
      (node (ref "Y3") (pin "3") (pinfunction "2_3") (pintype "passive"))
    )
    (net (code "46") (name "Net-(U2-XOSC_Q2)") (class "Default")
      (node (ref "C28") (pin "2") (pinfunction "2_2") (pintype "passive"))
      (node (ref "U2") (pin "31") (pinfunction "XOSC_Q2_31") (pintype "bidirectional"))
      (node (ref "Y3") (pin "1") (pinfunction "1_1") (pintype "passive"))
    )
    (net (code "47") (name "Net-(U4-3D-FIX)") (class "Default")
      (node (ref "D1") (pin "A") (pinfunction "A_A") (pintype "passive"))
      (node (ref "U4") (pin "P$5") (pinfunction "3D-FIX_P$5") (pintype "bidirectional"))
    )
    (net (code "48") (name "PROG") (class "Default")
      (node (ref "R13") (pin "2") (pinfunction "2_2") (pintype "passive"))
      (node (ref "S2") (pin "1") (pinfunction "1_1") (pintype "passive"))
      (node (ref "S2") (pin "2") (pinfunction "1_2") (pintype "passive"))
      (node (ref "U1") (pin "12") (pinfunction "PA07(AIN7/SER0:3/TC1:1)_12") (pintype "bidirectional"))
    )
    (net (code "49") (name "RAW") (class "Default")
      (node (ref "J1") (pin "2") (pinfunction "+_2") (pintype "bidirectional"))
      (node (ref "R18") (pin "2") (pinfunction "2_2") (pintype "passive"))
      (node (ref "U$1") (pin "VCC") (pinfunction "VCC_VCC") (pintype "bidirectional"))
      (node (ref "U$2") (pin "VCC") (pinfunction "VCC_VCC") (pintype "bidirectional"))
      (node (ref "U$3") (pin "S1") (pinfunction "S_S1") (pintype "bidirectional"))
      (node (ref "U$3") (pin "S2") (pinfunction "S_S2") (pintype "bidirectional"))
      (node (ref "U$3") (pin "S3") (pinfunction "S_S3") (pintype "bidirectional"))
    )
    (net (code "50") (name "SENSE_A") (class "Default")
      (node (ref "R10") (pin "2") (pinfunction "2_2") (pintype "passive"))
      (node (ref "R9") (pin "1") (pinfunction "1_1") (pintype "passive"))
      (node (ref "U1") (pin "7") (pinfunction "PB08(AIN2/SER4:0/TC4:0)_7") (pintype "bidirectional"))
    )
    (net (code "51") (name "SENSE_B") (class "Default")
      (node (ref "R11") (pin "2") (pinfunction "2_2") (pintype "passive"))
      (node (ref "R12") (pin "1") (pinfunction "1_1") (pintype "passive"))
      (node (ref "U1") (pin "8") (pinfunction "PB09(AIN3/SER4:1/TC4:1)_8") (pintype "bidirectional"))
    )
    (net (code "52") (name "SENSE_BAT") (class "Default")
      (node (ref "R18") (pin "1") (pinfunction "1_1") (pintype "passive"))
      (node (ref "R19") (pin "2") (pinfunction "2_2") (pintype "passive"))
      (node (ref "U1") (pin "11") (pinfunction "PA06(AIN6/SER0:2/TC1:0)_11") (pintype "bidirectional"))
    )
    (net (code "53") (name "SPI_MISO") (class "Default")
      (node (ref "MEM") (pin "SO") (pinfunction "SO_SO") (pintype "bidirectional"))
      (node (ref "U$5") (pin "6") (pinfunction "SDO_6") (pintype "bidirectional"))
      (node (ref "U1") (pin "23") (pinfunction "PA14(XIN/SER2:2+)_23") (pintype "bidirectional"))
      (node (ref "U2") (pin "9") (pinfunction "GPOI1_9") (pintype "bidirectional"))
      (node (ref "U3") (pin "12") (pinfunction "SDO_12") (pintype "bidirectional"))
    )
    (net (code "54") (name "SPI_MOSI") (class "Default")
      (node (ref "MEM") (pin "SI") (pinfunction "SI_SI") (pintype "bidirectional"))
      (node (ref "U$5") (pin "7") (pinfunction "SDI/SDA_7") (pintype "bidirectional"))
      (node (ref "U1") (pin "21") (pinfunction "PA12(I2C/SER2:0+)_21") (pintype "bidirectional"))
      (node (ref "U2") (pin "7") (pinfunction "SI_7") (pintype "bidirectional"))
      (node (ref "U3") (pin "13") (pinfunction "SDA_13") (pintype "bidirectional"))
    )
    (net (code "55") (name "SPI_SCK") (class "Default")
      (node (ref "MEM") (pin "SCK") (pinfunction "SCK_SCK") (pintype "bidirectional"))
      (node (ref "U$5") (pin "8") (pinfunction "SCLK_8") (pintype "bidirectional"))
      (node (ref "U1") (pin "24") (pinfunction "PA15(XOUT/SER2:3+)_24") (pintype "bidirectional"))
      (node (ref "U2") (pin "8") (pinfunction "SCLK_8") (pintype "bidirectional"))
      (node (ref "U3") (pin "14") (pinfunction "SCL_14") (pintype "bidirectional"))
    )
    (net (code "56") (name "SWCLK") (class "Default")
      (node (ref "JP1") (pin "4") (pinfunction "SWDCLK/TCK_4") (pintype "bidirectional"))
      (node (ref "U1") (pin "45") (pinfunction "PA30(SWCLK/SER1:2+)_45") (pintype "bidirectional"))
    )
    (net (code "57") (name "SWDIO") (class "Default")
      (node (ref "JP1") (pin "2") (pinfunction "SWDIO/TMS_2") (pintype "bidirectional"))
      (node (ref "U1") (pin "46") (pinfunction "PA31(SWDIO/SER1:3+)_46") (pintype "bidirectional"))
    )
    (net (code "58") (name "USB_D+") (class "Default")
      (node (ref "JP4") (pin "D+") (pinfunction "D+_D+") (pintype "bidirectional"))
      (node (ref "U1") (pin "34") (pinfunction "PA25(SER3:3+)_34") (pintype "bidirectional"))
    )
    (net (code "59") (name "USB_D-") (class "Default")
      (node (ref "JP4") (pin "D-") (pinfunction "D-_D-") (pintype "bidirectional"))
      (node (ref "U1") (pin "33") (pinfunction "PA24(SER3:2+)_33") (pintype "bidirectional"))
    )
    (net (code "60") (name "unconnected-(1U2-BP-Pad4)") (class "Default")
      (node (ref "1U2") (pin "4") (pinfunction "BP_4") (pintype "input"))
    )
    (net (code "61") (name "unconnected-(J1-PAD1-PadNC1)") (class "Default")
      (node (ref "J1") (pin "NC1") (pinfunction "PAD1_NC1") (pintype "bidirectional"))
    )
    (net (code "62") (name "unconnected-(J1-PAD2-PadNC2)") (class "Default")
      (node (ref "J1") (pin "NC2") (pinfunction "PAD2_NC2") (pintype "bidirectional"))
    )
    (net (code "63") (name "unconnected-(JP1-GNDDTCT-Pad9)") (class "Default")
      (node (ref "JP1") (pin "9") (pinfunction "GNDDTCT_9") (pintype "bidirectional"))
    )
    (net (code "64") (name "unconnected-(JP1-KEY-Pad7)") (class "Default")
      (node (ref "JP1") (pin "7") (pinfunction "KEY_7") (pintype "bidirectional"))
    )
    (net (code "65") (name "unconnected-(JP1-NC{slash}TDI-Pad8)") (class "Default")
      (node (ref "JP1") (pin "8") (pinfunction "NC/TDI_8") (pintype "bidirectional"))
    )
    (net (code "66") (name "unconnected-(JP1-SWO{slash}TDO-Pad6)") (class "Default")
      (node (ref "JP1") (pin "6") (pinfunction "SWO/TDO_6") (pintype "bidirectional"))
    )
    (net (code "67") (name "unconnected-(U$1-PadCLR)") (class "Default")
      (node (ref "U$1") (pin "CLR") (pinfunction "CLR_CLR") (pintype "bidirectional"))
    )
    (net (code "68") (name "unconnected-(U$1-~{OUT}-Pad!OUT)") (class "Default")
      (node (ref "U$1") (pin "!OUT") (pinfunction "~{OUT}_!OUT") (pintype "bidirectional"))
    )
    (net (code "69") (name "unconnected-(U1-PA02(AIN0{slash}DAC)-Pad3)") (class "Default")
      (node (ref "U1") (pin "3") (pinfunction "PA02(AIN0/DAC)_3") (pintype "bidirectional"))
    )
    (net (code "70") (name "unconnected-(U1-PA03(AIN1{slash}REFA)-Pad4)") (class "Default")
      (node (ref "U1") (pin "4") (pinfunction "PA03(AIN1/REFA)_4") (pintype "bidirectional"))
    )
    (net (code "71") (name "unconnected-(U1-PA04(AIN4{slash}REFB{slash}SER0:0{slash}TC0:0)-Pad9)") (class "Default")
      (node (ref "U1") (pin "9") (pinfunction "PA04(AIN4/REFB/SER0:0/TC0:0)_9") (pintype "bidirectional"))
    )
    (net (code "72") (name "unconnected-(U1-PA05(AIN5{slash}SER0:1{slash}TC0:1)-Pad10)") (class "Default")
      (node (ref "U1") (pin "10") (pinfunction "PA05(AIN5/SER0:1/TC0:1)_10") (pintype "bidirectional"))
    )
    (net (code "73") (name "unconnected-(U1-PA11(AIN19{slash}SER0:3+)-Pad16)") (class "Default")
      (node (ref "U1") (pin "16") (pinfunction "PA11(AIN19/SER0:3+)_16") (pintype "bidirectional"))
    )
    (net (code "74") (name "unconnected-(U1-PA17(I2C{slash}SER1:1+)-Pad26)") (class "Default")
      (node (ref "U1") (pin "26") (pinfunction "PA17(I2C/SER1:1+)_26") (pintype "bidirectional"))
    )
    (net (code "75") (name "unconnected-(U1-PA18(SER1:2+)-Pad27)") (class "Default")
      (node (ref "U1") (pin "27") (pinfunction "PA18(SER1:2+)_27") (pintype "bidirectional"))
    )
    (net (code "76") (name "unconnected-(U1-PA19(SER1:3+)-Pad28)") (class "Default")
      (node (ref "U1") (pin "28") (pinfunction "PA19(SER1:3+)_28") (pintype "bidirectional"))
    )
    (net (code "77") (name "unconnected-(U1-PA20(SER5:2+)-Pad29)") (class "Default")
      (node (ref "U1") (pin "29") (pinfunction "PA20(SER5:2+)_29") (pintype "bidirectional"))
    )
    (net (code "78") (name "unconnected-(U1-PA21(SER5:3+)-Pad30)") (class "Default")
      (node (ref "U1") (pin "30") (pinfunction "PA21(SER5:3+)_30") (pintype "bidirectional"))
    )
    (net (code "79") (name "unconnected-(U1-PA22(I2C{slash}SER3:0+)-Pad31)") (class "Default")
      (node (ref "U1") (pin "31") (pinfunction "PA22(I2C/SER3:0+)_31") (pintype "bidirectional"))
    )
    (net (code "80") (name "unconnected-(U1-PA23(I2C{slash}SER3:0+)-Pad32)") (class "Default")
      (node (ref "U1") (pin "32") (pinfunction "PA23(I2C/SER3:0+)_32") (pintype "bidirectional"))
    )
    (net (code "81") (name "unconnected-(U1-PA27-Pad39)") (class "Default")
      (node (ref "U1") (pin "39") (pinfunction "PA27_39") (pintype "bidirectional"))
    )
    (net (code "82") (name "unconnected-(U1-PA28-Pad41)") (class "Default")
      (node (ref "U1") (pin "41") (pinfunction "PA28_41") (pintype "bidirectional"))
    )
    (net (code "83") (name "unconnected-(U1-PB10(SER4:2+)-Pad19)") (class "Default")
      (node (ref "U1") (pin "19") (pinfunction "PB10(SER4:2+)_19") (pintype "bidirectional"))
    )
    (net (code "84") (name "unconnected-(U1-PB11(SER4:3+)-Pad20)") (class "Default")
      (node (ref "U1") (pin "20") (pinfunction "PB11(SER4:3+)_20") (pintype "bidirectional"))
    )
    (net (code "85") (name "unconnected-(U2-GPIO0-Pad10)") (class "Default")
      (node (ref "U2") (pin "10") (pinfunction "GPIO0_10") (pintype "bidirectional"))
    )
    (net (code "86") (name "unconnected-(U2-GPIO2-Pad4)") (class "Default")
      (node (ref "U2") (pin "4") (pinfunction "GPIO2_4") (pintype "bidirectional"))
    )
    (net (code "87") (name "unconnected-(U2-GPIO3-Pad3)") (class "Default")
      (node (ref "U2") (pin "3") (pinfunction "GPIO3_3") (pintype "bidirectional"))
    )
    (net (code "88") (name "unconnected-(U2-N.C.-Pad16)") (class "Default")
      (node (ref "U2") (pin "16") (pinfunction "N.C._16") (pintype "bidirectional"))
    )
    (net (code "89") (name "unconnected-(U2-RESET_N-Pad2)") (class "Default")
      (node (ref "U2") (pin "2") (pinfunction "RESET_N_2") (pintype "bidirectional"))
    )
    (net (code "90") (name "unconnected-(U3-INT1-Pad8)") (class "Default")
      (node (ref "U3") (pin "8") (pinfunction "INT1_8") (pintype "bidirectional"))
    )
    (net (code "91") (name "unconnected-(U3-INT2-Pad9)") (class "Default")
      (node (ref "U3") (pin "9") (pinfunction "INT2_9") (pintype "bidirectional"))
    )
    (net (code "92") (name "unconnected-(U3-NC-Pad3)") (class "Default")
      (node (ref "U3") (pin "3") (pinfunction "NC_3") (pintype "bidirectional"))
    )
    (net (code "93") (name "unconnected-(U3-NC-Pad10)") (class "Default")
      (node (ref "U3") (pin "10") (pinfunction "NC_10") (pintype "bidirectional"))
    )
    (net (code "94") (name "unconnected-(U3-NC-Pad11)") (class "Default")
      (node (ref "U3") (pin "11") (pinfunction "NC_11") (pintype "bidirectional"))
    )
    (net (code "95") (name "unconnected-(U4-1PPS-PadP$13)") (class "Default")
      (node (ref "U4") (pin "P$13") (pinfunction "1PPS_P$13") (pintype "bidirectional"))
    )
    (net (code "96") (name "unconnected-(U4-EX_ANT-PadP$11)") (class "Default")
      (node (ref "U4") (pin "P$11") (pinfunction "EX_ANT_P$11") (pintype "bidirectional"))
    )
    (net (code "97") (name "unconnected-(U4-NC-PadP$6)") (class "Default")
      (node (ref "U4") (pin "P$6") (pinfunction "NC_P$6") (pintype "bidirectional"))
    )
    (net (code "98") (name "unconnected-(U4-NC-PadP$7)") (class "Default")
      (node (ref "U4") (pin "P$7") (pinfunction "NC_P$7") (pintype "bidirectional"))
    )
    (net (code "99") (name "unconnected-(U4-NC-PadP$15)") (class "Default")
      (node (ref "U4") (pin "P$15") (pinfunction "NC_P$15") (pintype "bidirectional"))
    )
    (net (code "100") (name "unconnected-(U4-NC-PadP$16)") (class "Default")
      (node (ref "U4") (pin "P$16") (pinfunction "NC_P$16") (pintype "bidirectional"))
    )
    (net (code "101") (name "unconnected-(U4-NC-PadP$17)") (class "Default")
      (node (ref "U4") (pin "P$17") (pinfunction "NC_P$17") (pintype "bidirectional"))
    )
    (net (code "102") (name "unconnected-(U4-NC-PadP$18)") (class "Default")
      (node (ref "U4") (pin "P$18") (pinfunction "NC_P$18") (pintype "bidirectional"))
    )
    (net (code "103") (name "unconnected-(U4-NC-PadP$20)") (class "Default")
      (node (ref "U4") (pin "P$20") (pinfunction "NC_P$20") (pintype "bidirectional"))
    )
    (net (code "104") (name "unconnected-(U4-NRESET-PadP$2)") (class "Default")
      (node (ref "U4") (pin "P$2") (pinfunction "NRESET_P$2") (pintype "bidirectional"))
    )
    (net (code "105") (name "unconnected-(U4-RTCM-PadP$14)") (class "Default")
      (node (ref "U4") (pin "P$14") (pinfunction "RTCM_P$14") (pintype "bidirectional"))
    )
    (net (code "106") (name "unconnected-(U4-VBACKUP-PadP$4)") (class "Default")
      (node (ref "U4") (pin "P$4") (pinfunction "VBACKUP_P$4") (pintype "bidirectional"))
    )
  )
)
